# STM32.net
KiCad netlist of a schematic drawn in Altium Designer
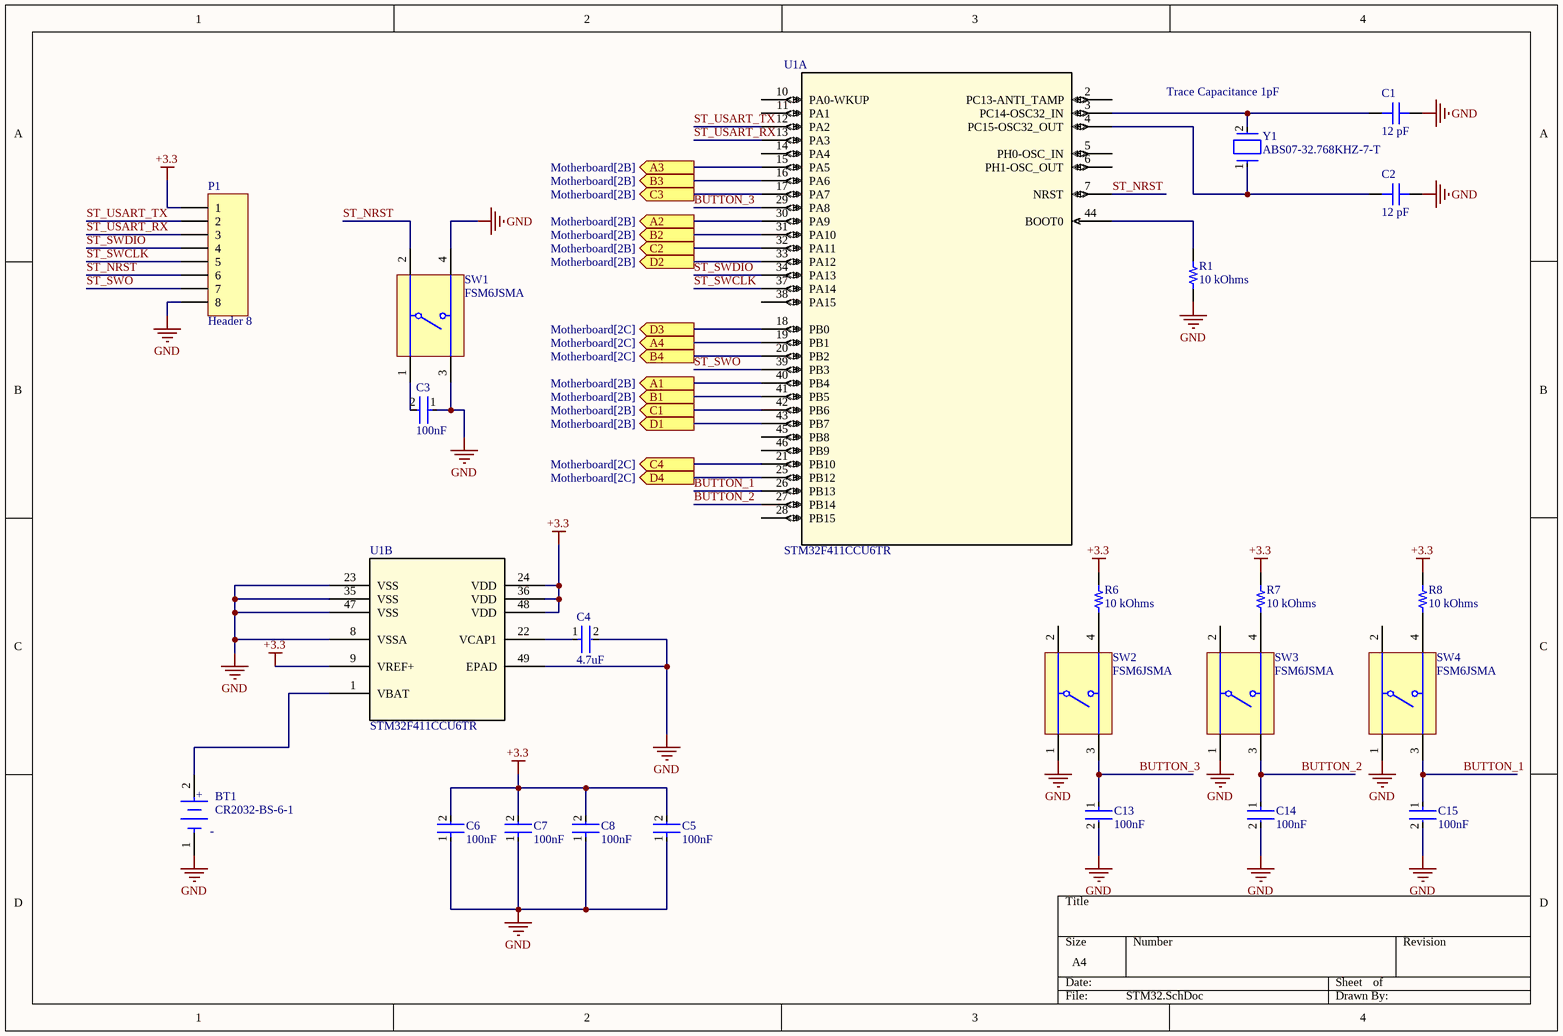
[diagram p0: STM32.SchDoc]

(export (version "E")
  (design (tool "Eeschema 10.0.6"))
  (components
    (comp (ref "BT1")
      (value "CR2032-BS-6-1")
      (footprint "FP-BU2032SM-BT-GTR-MFG")
      (libsource (lib "Altium Content Vault") (part "60d3b5b901a8747834971d0eb8cf3fd"))
    )
    (comp (ref "C1")
      (value "12 pF")
      (footprint "CAP 0201_0603")
      (description "CAP CER 10PF 25V C0G/NP0 0201")
      (fields (field (name "PART NUMBER") "C0201C100J3GAC7867") (field (name "MANUFACTURER") "KEMET"))
      (libsource (lib "Celestial Altium Library - altium_library") (part "Capacitor"))
    )
    (comp (ref "C2")
      (value "12 pF")
      (footprint "CAP 0201_0603")
      (description "CAP CER 10PF 25V C0G/NP0 0201")
      (fields (field (name "PART NUMBER") "C0201C100J3GAC7867") (field (name "MANUFACTURER") "KEMET"))
      (libsource (lib "Celestial Altium Library - altium_library") (part "Capacitor"))
    )
    (comp (ref "C3")
      (value "100nF")
      (footprint "FP-C1005-050-0_15-MFG")
      (description "CAP CER 100nF 10V X5R 0402")
      (fields (field (name "TOLERANCE") "20%") (field (name "VOLTAGE") "10V"))
      (libsource (lib "Altium Content Vault") (part "11868f565c42a9108669ba33697ecf6"))
    )
    (comp (ref "C4")
      (value "4.7uF")
      (footprint "FP-C1005-050-0_15-MFG")
      (description "CAP CER 4.7UF 10V X5R 0402")
      (fields (field (name "TOLERANCE") "20%") (field (name "VOLTAGE") "10V"))
      (libsource (lib "Altium Content Vault") (part "11868f565c42a9108669ba33697ecf6"))
    )
    (comp (ref "C5")
      (value "100nF")
      (footprint "FP-C1005-050-0_15-MFG")
      (description "CAP CER 100nF 10V X5R 0402")
      (fields (field (name "TOLERANCE") "20%") (field (name "VOLTAGE") "10V"))
      (libsource (lib "Altium Content Vault") (part "11868f565c42a9108669ba33697ecf6"))
    )
    (comp (ref "C6")
      (value "100nF")
      (footprint "FP-C1005-050-0_15-MFG")
      (description "CAP CER 100nF 10V X5R 0402")
      (fields (field (name "TOLERANCE") "20%") (field (name "VOLTAGE") "10V"))
      (libsource (lib "Altium Content Vault") (part "11868f565c42a9108669ba33697ecf6"))
    )
    (comp (ref "C7")
      (value "100nF")
      (footprint "FP-C1005-050-0_15-MFG")
      (description "CAP CER 100nF 10V X5R 0402")
      (fields (field (name "TOLERANCE") "20%") (field (name "VOLTAGE") "10V"))
      (libsource (lib "Altium Content Vault") (part "11868f565c42a9108669ba33697ecf6"))
    )
    (comp (ref "C8")
      (value "100nF")
      (footprint "FP-C1005-050-0_15-MFG")
      (description "CAP CER 100nF 10V X5R 0402")
      (fields (field (name "TOLERANCE") "20%") (field (name "VOLTAGE") "10V"))
      (libsource (lib "Altium Content Vault") (part "11868f565c42a9108669ba33697ecf6"))
    )
    (comp (ref "C13")
      (value "100nF")
      (footprint "FP-C1005-050-0_15-MFG")
      (description "CAP CER 100nF 10V X5R 0402")
      (fields (field (name "TOLERANCE") "20%") (field (name "VOLTAGE") "10V"))
      (libsource (lib "Altium Content Vault") (part "11868f565c42a9108669ba33697ecf6"))
    )
    (comp (ref "C14")
      (value "100nF")
      (footprint "FP-C1005-050-0_15-MFG")
      (description "CAP CER 100nF 10V X5R 0402")
      (fields (field (name "TOLERANCE") "20%") (field (name "VOLTAGE") "10V"))
      (libsource (lib "Altium Content Vault") (part "11868f565c42a9108669ba33697ecf6"))
    )
    (comp (ref "C15")
      (value "100nF")
      (footprint "FP-C1005-050-0_15-MFG")
      (description "CAP CER 100nF 10V X5R 0402")
      (fields (field (name "TOLERANCE") "20%") (field (name "VOLTAGE") "10V"))
      (libsource (lib "Altium Content Vault") (part "11868f565c42a9108669ba33697ecf6"))
    )
    (comp (ref "P1")
      (value "Header 8")
      (footprint "HDR1X8")
      (description "Header, 8-Pin")
      (fields (field (name "PUBLISHER") "Altium Limited"))
      (libsource (lib "Miscellaneous Connectors") (part "Header 8"))
    )
    (comp (ref "R1")
      (value "10 kOhms")
      (footprint "RES 0402_1005")
      (description "RES 10K OHM 1% 1/16W 0402")
      (fields (field (name "PART NUMBER") "TNPW040210K0BETD") (field (name "MANUFACTURER") "Vishay Dale"))
      (libsource (lib "Celestial Altium Library - altium_library") (part "Resistor"))
    )
    (comp (ref "R6")
      (value "10 kOhms")
      (footprint "RES 0402_1005")
      (description "RES 10K OHM 1% 1/16W 0402")
      (fields (field (name "PART NUMBER") "TNPW040210K0BETD") (field (name "MANUFACTURER") "Vishay Dale"))
      (libsource (lib "Celestial Altium Library - altium_library") (part "Resistor"))
    )
    (comp (ref "R7")
      (value "10 kOhms")
      (footprint "RES 0402_1005")
      (description "RES 10K OHM 1% 1/16W 0402")
      (fields (field (name "PART NUMBER") "TNPW040210K0BETD") (field (name "MANUFACTURER") "Vishay Dale"))
      (libsource (lib "Celestial Altium Library - altium_library") (part "Resistor"))
    )
    (comp (ref "R8")
      (value "10 kOhms")
      (footprint "RES 0402_1005")
      (description "RES 10K OHM 1% 1/16W 0402")
      (fields (field (name "PART NUMBER") "TNPW040210K0BETD") (field (name "MANUFACTURER") "Vishay Dale"))
      (libsource (lib "Celestial Altium Library - altium_library") (part "Resistor"))
    )
    (comp (ref "SW1")
      (value "FSM6JSMA")
      (footprint "TECO-FSM6JSMA_V")
      (description "Switch, SPST, 24 V, -35 to 85 degC, 4-Pin SMD, RoHS, Tape and Reel")
      (fields (field (name "MANUFACTURER") "TE Connectivity"))
      (libsource (lib "Altium Content Vault") (part "SW-SPST-4_A"))
    )
    (comp (ref "SW2")
      (value "FSM6JSMA")
      (footprint "TECO-FSM6JSMA_V")
      (description "Switch, SPST, 24 V, -35 to 85 degC, 4-Pin SMD, RoHS, Tape and Reel")
      (fields (field (name "MANUFACTURER") "TE Connectivity"))
      (libsource (lib "Altium Content Vault") (part "SW-SPST-4_A"))
    )
    (comp (ref "SW3")
      (value "FSM6JSMA")
      (footprint "TECO-FSM6JSMA_V")
      (description "Switch, SPST, 24 V, -35 to 85 degC, 4-Pin SMD, RoHS, Tape and Reel")
      (fields (field (name "MANUFACTURER") "TE Connectivity"))
      (libsource (lib "Altium Content Vault") (part "SW-SPST-4_A"))
    )
    (comp (ref "SW4")
      (value "FSM6JSMA")
      (footprint "TECO-FSM6JSMA_V")
      (description "Switch, SPST, 24 V, -35 to 85 degC, 4-Pin SMD, RoHS, Tape and Reel")
      (fields (field (name "MANUFACTURER") "TE Connectivity"))
      (libsource (lib "Altium Content Vault") (part "SW-SPST-4_A"))
    )
    (comp (ref "U1")
      (value "STM32F411CCU6TR")
      (footprint "UFQFPN-48_7X7X0P55MM")
      (description "No Description Available")
      (fields (field (name "COPYRIGHT") "Copyright (C) 2023 Ultra Librarian. All rights reserved."))
      (libsource (lib "STM32F411CCU6TR") (part "STM32F411CCU6TR"))
    )
    (comp (ref "Y1")
      (value "ABS07-32.768KHZ-7-T")
      (footprint "FP-ABS07-MFG")
      (description "Crystal 32.768kHz ±20ppm (Tol) 9pF FUND 70kΩ 2-Pin CSMD T/R")
      (fields (field (name "TOLERANCE") "20ppm"))
      (libsource (lib "Altium Content Vault") (part "c23a69dc6c9e2f18f2079038eb95dd1"))
    )
  )
  (nets
    (net (code "1") (name "+3.3") (class "Default")
      (node (ref "C5") (pin "2") (pinfunction "2_2") (pintype "passive"))
      (node (ref "C6") (pin "2") (pinfunction "2_2") (pintype "passive"))
      (node (ref "C7") (pin "2") (pinfunction "2_2") (pintype "passive"))
      (node (ref "C8") (pin "2") (pinfunction "2_2") (pintype "passive"))
      (node (ref "P1") (pin "1") (pinfunction "1_1") (pintype "passive"))
      (node (ref "R6") (pin "2") (pinfunction "2_2") (pintype "passive"))
      (node (ref "R7") (pin "2") (pinfunction "2_2") (pintype "passive"))
      (node (ref "R8") (pin "2") (pinfunction "2_2") (pintype "passive"))
      (node (ref "U1") (pin "24") (pinfunction "VDD_24") (pintype "power_in"))
      (node (ref "U1") (pin "36") (pinfunction "VDD_36") (pintype "power_in"))
      (node (ref "U1") (pin "48") (pinfunction "VDD_48") (pintype "power_in"))
      (node (ref "U1") (pin "9") (pinfunction "VREF+_9") (pintype "power_in"))
    )
    (net (code "2") (name "/A1") (class "Default")
      (node (ref "U1") (pin "40") (pinfunction "PB4_40") (pintype "bidirectional"))
    )
    (net (code "3") (name "/A2") (class "Default")
      (node (ref "U1") (pin "30") (pinfunction "PA9_30") (pintype "bidirectional"))
    )
    (net (code "4") (name "/A3") (class "Default")
      (node (ref "U1") (pin "15") (pinfunction "PA5_15") (pintype "bidirectional"))
    )
    (net (code "5") (name "/A4") (class "Default")
      (node (ref "U1") (pin "19") (pinfunction "PB1_19") (pintype "bidirectional"))
    )
    (net (code "6") (name "/B1") (class "Default")
      (node (ref "U1") (pin "41") (pinfunction "PB5_41") (pintype "bidirectional"))
    )
    (net (code "7") (name "/B2") (class "Default")
      (node (ref "U1") (pin "31") (pinfunction "PA10_31") (pintype "bidirectional"))
    )
    (net (code "8") (name "/B3") (class "Default")
      (node (ref "U1") (pin "16") (pinfunction "PA6_16") (pintype "bidirectional"))
    )
    (net (code "9") (name "/B4") (class "Default")
      (node (ref "U1") (pin "20") (pinfunction "PB2_20") (pintype "bidirectional"))
    )
    (net (code "10") (name "/BUTTON_1") (class "Default")
      (node (ref "C15") (pin "1") (pinfunction "1_1") (pintype "passive"))
      (node (ref "SW4") (pin "3") (pinfunction "3_3") (pintype "passive"))
      (node (ref "U1") (pin "26") (pinfunction "PB13_26") (pintype "bidirectional"))
    )
    (net (code "11") (name "/BUTTON_2") (class "Default")
      (node (ref "C14") (pin "1") (pinfunction "1_1") (pintype "passive"))
      (node (ref "SW3") (pin "3") (pinfunction "3_3") (pintype "passive"))
      (node (ref "U1") (pin "27") (pinfunction "PB14_27") (pintype "bidirectional"))
    )
    (net (code "12") (name "/BUTTON_3") (class "Default")
      (node (ref "C13") (pin "1") (pinfunction "1_1") (pintype "passive"))
      (node (ref "SW2") (pin "3") (pinfunction "3_3") (pintype "passive"))
      (node (ref "U1") (pin "29") (pinfunction "PA8_29") (pintype "bidirectional"))
    )
    (net (code "13") (name "/C1") (class "Default")
      (node (ref "U1") (pin "42") (pinfunction "PB6_42") (pintype "bidirectional"))
    )
    (net (code "14") (name "/C2") (class "Default")
      (node (ref "U1") (pin "32") (pinfunction "PA11_32") (pintype "bidirectional"))
    )
    (net (code "15") (name "/C3") (class "Default")
      (node (ref "U1") (pin "17") (pinfunction "PA7_17") (pintype "bidirectional"))
    )
    (net (code "16") (name "/C4") (class "Default")
      (node (ref "U1") (pin "21") (pinfunction "PB10_21") (pintype "bidirectional"))
    )
    (net (code "17") (name "/D1") (class "Default")
      (node (ref "U1") (pin "43") (pinfunction "PB7_43") (pintype "bidirectional"))
    )
    (net (code "18") (name "/D2") (class "Default")
      (node (ref "U1") (pin "33") (pinfunction "PA12_33") (pintype "bidirectional"))
    )
    (net (code "19") (name "/D3") (class "Default")
      (node (ref "U1") (pin "18") (pinfunction "PB0_18") (pintype "bidirectional"))
    )
    (net (code "20") (name "/D4") (class "Default")
      (node (ref "U1") (pin "25") (pinfunction "PB12_25") (pintype "bidirectional"))
    )
    (net (code "21") (name "/ST_NRST") (class "Default")
      (node (ref "P1") (pin "6") (pinfunction "6_6") (pintype "passive"))
      (node (ref "SW1") (pin "2") (pinfunction "2_2") (pintype "passive"))
      (node (ref "U1") (pin "7") (pinfunction "NRST_7") (pintype "bidirectional"))
    )
    (net (code "22") (name "/ST_SWCLK") (class "Default")
      (node (ref "P1") (pin "5") (pinfunction "5_5") (pintype "passive"))
      (node (ref "U1") (pin "37") (pinfunction "PA14_37") (pintype "bidirectional"))
    )
    (net (code "23") (name "/ST_SWDIO") (class "Default")
      (node (ref "P1") (pin "4") (pinfunction "4_4") (pintype "passive"))
      (node (ref "U1") (pin "34") (pinfunction "PA13_34") (pintype "bidirectional"))
    )
    (net (code "24") (name "/ST_SWO") (class "Default")
      (node (ref "P1") (pin "7") (pinfunction "7_7") (pintype "passive"))
      (node (ref "U1") (pin "39") (pinfunction "PB3_39") (pintype "bidirectional"))
    )
    (net (code "25") (name "/ST_USART_RX") (class "Default")
      (node (ref "P1") (pin "3") (pinfunction "3_3") (pintype "passive"))
      (node (ref "U1") (pin "13") (pinfunction "PA3_13") (pintype "bidirectional"))
    )
    (net (code "26") (name "/ST_USART_TX") (class "Default")
      (node (ref "P1") (pin "2") (pinfunction "2_2") (pintype "passive"))
      (node (ref "U1") (pin "12") (pinfunction "PA2_12") (pintype "bidirectional"))
    )
    (net (code "27") (name "GND") (class "Default")
      (node (ref "BT1") (pin "1") (pinfunction "C_1") (pintype "passive"))
      (node (ref "C1") (pin "2") (pinfunction "2_2") (pintype "passive"))
      (node (ref "C13") (pin "2") (pinfunction "2_2") (pintype "passive"))
      (node (ref "C14") (pin "2") (pinfunction "2_2") (pintype "passive"))
      (node (ref "C15") (pin "2") (pinfunction "2_2") (pintype "passive"))
      (node (ref "C2") (pin "2") (pinfunction "2_2") (pintype "passive"))
      (node (ref "C3") (pin "1") (pinfunction "1_1") (pintype "passive"))
      (node (ref "C4") (pin "2") (pinfunction "2_2") (pintype "passive"))
      (node (ref "C5") (pin "1") (pinfunction "1_1") (pintype "passive"))
      (node (ref "C6") (pin "1") (pinfunction "1_1") (pintype "passive"))
      (node (ref "C7") (pin "1") (pinfunction "1_1") (pintype "passive"))
      (node (ref "C8") (pin "1") (pinfunction "1_1") (pintype "passive"))
      (node (ref "P1") (pin "8") (pinfunction "8_8") (pintype "passive"))
      (node (ref "R1") (pin "1") (pinfunction "1_1") (pintype "passive"))
      (node (ref "SW1") (pin "3") (pinfunction "3_3") (pintype "passive"))
      (node (ref "SW1") (pin "4") (pinfunction "4_4") (pintype "passive"))
      (node (ref "SW2") (pin "1") (pinfunction "1_1") (pintype "passive"))
      (node (ref "SW3") (pin "1") (pinfunction "1_1") (pintype "passive"))
      (node (ref "SW4") (pin "1") (pinfunction "1_1") (pintype "passive"))
      (node (ref "U1") (pin "23") (pinfunction "VSS_23") (pintype "power_in"))
      (node (ref "U1") (pin "35") (pinfunction "VSS_35") (pintype "power_in"))
      (node (ref "U1") (pin "47") (pinfunction "VSS_47") (pintype "power_in"))
      (node (ref "U1") (pin "49") (pinfunction "EPAD_49") (pintype "passive"))
      (node (ref "U1") (pin "8") (pinfunction "VSSA_8") (pintype "power_in"))
    )
    (net (code "28") (name "Net-(BT1-A)") (class "Default")
      (node (ref "BT1") (pin "2") (pinfunction "A_2") (pintype "passive"))
      (node (ref "U1") (pin "1") (pinfunction "VBAT_1") (pintype "power_in"))
    )
    (net (code "29") (name "Net-(C3-Pad2)") (class "Default")
      (node (ref "C3") (pin "2") (pinfunction "2_2") (pintype "passive"))
      (node (ref "SW1") (pin "1") (pinfunction "1_1") (pintype "passive"))
    )
    (net (code "30") (name "Net-(R6-Pad1)") (class "Default")
      (node (ref "R6") (pin "1") (pinfunction "1_1") (pintype "passive"))
      (node (ref "SW2") (pin "4") (pinfunction "4_4") (pintype "passive"))
    )
    (net (code "31") (name "Net-(R7-Pad1)") (class "Default")
      (node (ref "R7") (pin "1") (pinfunction "1_1") (pintype "passive"))
      (node (ref "SW3") (pin "4") (pinfunction "4_4") (pintype "passive"))
    )
    (net (code "32") (name "Net-(R8-Pad1)") (class "Default")
      (node (ref "R8") (pin "1") (pinfunction "1_1") (pintype "passive"))
      (node (ref "SW4") (pin "4") (pinfunction "4_4") (pintype "passive"))
    )
    (net (code "33") (name "Net-(U1A-BOOT0)") (class "Default")
      (node (ref "R1") (pin "2") (pinfunction "2_2") (pintype "passive"))
      (node (ref "U1") (pin "44") (pinfunction "BOOT0_44") (pintype "input"))
    )
    (net (code "34") (name "Net-(U1A-PC14-OSC32_IN)") (class "Default")
      (node (ref "C1") (pin "1") (pinfunction "1_1") (pintype "passive"))
      (node (ref "U1") (pin "3") (pinfunction "PC14-OSC32_IN_3") (pintype "bidirectional"))
      (node (ref "Y1") (pin "2") (pinfunction "2_2") (pintype "passive"))
    )
    (net (code "35") (name "Net-(U1A-PC15-OSC32_OUT)") (class "Default")
      (node (ref "C2") (pin "1") (pinfunction "1_1") (pintype "passive"))
      (node (ref "U1") (pin "4") (pinfunction "PC15-OSC32_OUT_4") (pintype "bidirectional"))
      (node (ref "Y1") (pin "1") (pinfunction "1_1") (pintype "passive"))
    )
    (net (code "36") (name "Net-(U1B-VCAP1)") (class "Default")
      (node (ref "C4") (pin "1") (pinfunction "1_1") (pintype "passive"))
      (node (ref "U1") (pin "22") (pinfunction "VCAP1_22") (pintype "power_in"))
    )
    (net (code "37") (name "unconnected-(SW2-Pad2)") (class "Default")
      (node (ref "SW2") (pin "2") (pinfunction "2_2") (pintype "passive"))
    )
    (net (code "38") (name "unconnected-(SW3-Pad2)") (class "Default")
      (node (ref "SW3") (pin "2") (pinfunction "2_2") (pintype "passive"))
    )
    (net (code "39") (name "unconnected-(SW4-Pad2)") (class "Default")
      (node (ref "SW4") (pin "2") (pinfunction "2_2") (pintype "passive"))
    )
    (net (code "40") (name "unconnected-(U1A-PA0-WKUP-Pad10)") (class "Default")
      (node (ref "U1") (pin "10") (pinfunction "PA0-WKUP_10") (pintype "bidirectional"))
    )
    (net (code "41") (name "unconnected-(U1A-PA1-Pad11)") (class "Default")
      (node (ref "U1") (pin "11") (pinfunction "PA1_11") (pintype "bidirectional"))
    )
    (net (code "42") (name "unconnected-(U1A-PA4-Pad14)") (class "Default")
      (node (ref "U1") (pin "14") (pinfunction "PA4_14") (pintype "bidirectional"))
    )
    (net (code "43") (name "unconnected-(U1A-PA15-Pad38)") (class "Default")
      (node (ref "U1") (pin "38") (pinfunction "PA15_38") (pintype "bidirectional"))
    )
    (net (code "44") (name "unconnected-(U1A-PB8-Pad45)") (class "Default")
      (node (ref "U1") (pin "45") (pinfunction "PB8_45") (pintype "bidirectional"))
    )
    (net (code "45") (name "unconnected-(U1A-PB9-Pad46)") (class "Default")
      (node (ref "U1") (pin "46") (pinfunction "PB9_46") (pintype "bidirectional"))
    )
    (net (code "46") (name "unconnected-(U1A-PB15-Pad28)") (class "Default")
      (node (ref "U1") (pin "28") (pinfunction "PB15_28") (pintype "bidirectional"))
    )
    (net (code "47") (name "unconnected-(U1A-PC13-ANTI_TAMP-Pad2)") (class "Default")
      (node (ref "U1") (pin "2") (pinfunction "PC13-ANTI_TAMP_2") (pintype "bidirectional"))
    )
    (net (code "48") (name "unconnected-(U1A-PH0-OSC_IN-Pad5)") (class "Default")
      (node (ref "U1") (pin "5") (pinfunction "PH0-OSC_IN_5") (pintype "bidirectional"))
    )
    (net (code "49") (name "unconnected-(U1A-PH1-OSC_OUT-Pad6)") (class "Default")
      (node (ref "U1") (pin "6") (pinfunction "PH1-OSC_OUT_6") (pintype "bidirectional"))
    )
  )
)
